# Connectors.net
KiCad netlist of a schematic drawn in Altium Designer
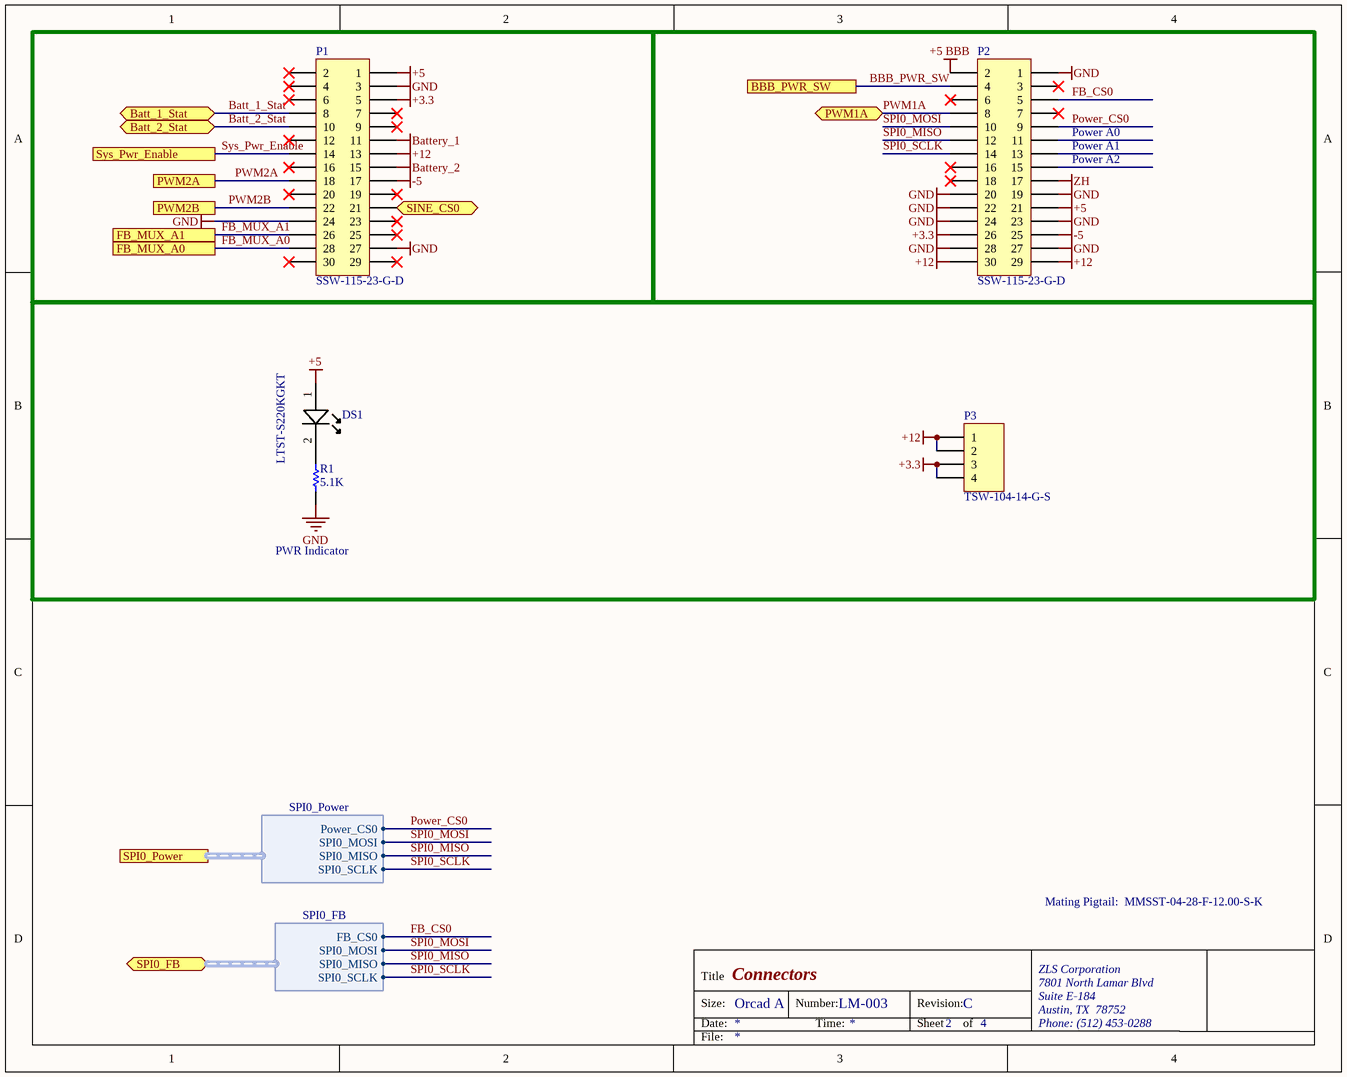
[diagram p0: Connectors.SchDoc]

(export (version "E")
  (design (tool "Eeschema 10.0.6"))
  (components
    (comp (ref "DS1")
      (value "Lite-On LTST-S220KGKT Green LED, 571 nm 2012 (0805) Side View, Rectangle Lens SMD package")
      (footprint "0805C_L")
      (fields
        (field (name "MANUFACTURER") "Vishay / Lite-On")
        (field (name "MANUFACTURER PART NUMBER") "LTST-S220KGKT")
      )
      (libsource (lib "*") (part "LED A/K"))
    )
    (comp (ref "P1")
      (value "SSW-115-23-G-D")
      (footprint "SSW-115-23-G-D")
      (description "Header, 15-Pin, Dual row")
      (fields (field (name "MANUFACTURER") "Samtec Inc."))
      (libsource (lib "Miscellaneous Connectors") (part "Header 15X2"))
    )
    (comp (ref "P2")
      (value "SSW-115-23-G-D")
      (footprint "SSW-115-23-G-D")
      (description "Header, 15-Pin, Dual row")
      (fields (field (name "MANUFACTURER") "Samtec Inc."))
      (libsource (lib "Miscellaneous Connectors") (part "Header 15X2"))
    )
    (comp (ref "P3")
      (value "TSW-104-14-G-S")
      (footprint "HDR1X4")
      (description "Header, 4-Pin")
      (fields (field (name "MANUFACTURER") "Samtec Inc."))
      (libsource (lib "Miscellaneous Connectors") (part "Header 4"))
    )
    (comp (ref "R1")
      (value "5.1K")
      (footprint "RESC0805(2012)_L")
      (description "RES SMD 5.1K OHM 5% 1/8W 0805")
      (fields
        (field (name "MANUFACTURER") "Vishay Dale")
        (field (name "MANUFACTURER PART NUMBER") "CRCW08055K10JNEA")
      )
      (libsource (lib "Altium Content Vault") (part "CMP-1013-00215-1"))
    )
  )
  (nets
    (net (code "3") (name "+3.3") (class "Default")
      (node (ref "P1") (pin "5") (pinfunction "5_5") (pintype "passive"))
      (node (ref "P2") (pin "26") (pinfunction "26_26") (pintype "passive"))
      (node (ref "P3") (pin "3") (pinfunction "3_3") (pintype "passive"))
      (node (ref "P3") (pin "4") (pinfunction "4_4") (pintype "passive"))
    )
    (net (code "4") (name "+5") (class "Default")
      (node (ref "DS1") (pin "1") (pinfunction "A_1") (pintype "passive"))
      (node (ref "P1") (pin "1") (pinfunction "1_1") (pintype "passive"))
      (node (ref "P2") (pin "21") (pinfunction "21_21") (pintype "passive"))
    )
    (net (code "5") (name "+5 BBB") (class "Default")
      (node (ref "P2") (pin "2") (pinfunction "2_2") (pintype "passive"))
    )
    (net (code "6") (name "+12") (class "Default")
      (node (ref "P1") (pin "13") (pinfunction "13_13") (pintype "passive"))
      (node (ref "P2") (pin "29") (pinfunction "29_29") (pintype "passive"))
      (node (ref "P2") (pin "30") (pinfunction "30_30") (pintype "passive"))
      (node (ref "P3") (pin "1") (pinfunction "1_1") (pintype "passive"))
      (node (ref "P3") (pin "2") (pinfunction "2_2") (pintype "passive"))
    )
    (net (code "7") (name "-5") (class "Default")
      (node (ref "P1") (pin "17") (pinfunction "17_17") (pintype "passive"))
      (node (ref "P2") (pin "25") (pinfunction "25_25") (pintype "passive"))
    )
    (net (code "8") (name "/BBB_PWR_SW") (class "Default")
      (node (ref "P2") (pin "4") (pinfunction "4_4") (pintype "passive"))
    )
    (net (code "9") (name "/Batt_1_Stat") (class "Default")
      (node (ref "P1") (pin "8") (pinfunction "8_8") (pintype "passive"))
    )
    (net (code "10") (name "/Batt_2_Stat") (class "Default")
      (node (ref "P1") (pin "10") (pinfunction "10_10") (pintype "passive"))
    )
    (net (code "11") (name "/FB_CS0") (class "Default")
      (node (ref "P2") (pin "5") (pinfunction "5_5") (pintype "passive"))
    )
    (net (code "12") (name "/FB_MUX_A0") (class "Default")
      (node (ref "P1") (pin "28") (pinfunction "28_28") (pintype "passive"))
    )
    (net (code "13") (name "/FB_MUX_A1") (class "Default")
      (node (ref "P1") (pin "26") (pinfunction "26_26") (pintype "passive"))
    )
    (net (code "14") (name "/PWM1A") (class "Default")
      (node (ref "P2") (pin "8") (pinfunction "8_8") (pintype "passive"))
    )
    (net (code "15") (name "/PWM2A") (class "Default")
      (node (ref "P1") (pin "18") (pinfunction "18_18") (pintype "passive"))
    )
    (net (code "16") (name "/PWM2B") (class "Default")
      (node (ref "P1") (pin "22") (pinfunction "22_22") (pintype "passive"))
    )
    (net (code "17") (name "/Power_CS0") (class "Default")
      (node (ref "P2") (pin "9") (pinfunction "9_9") (pintype "passive"))
    )
    (net (code "18") (name "/SINE_CS0") (class "Default")
      (node (ref "P1") (pin "21") (pinfunction "21_21") (pintype "passive"))
    )
    (net (code "19") (name "/SPI0_MISO") (class "Default")
      (node (ref "P2") (pin "12") (pinfunction "12_12") (pintype "passive"))
    )
    (net (code "20") (name "/SPI0_MOSI") (class "Default")
      (node (ref "P2") (pin "10") (pinfunction "10_10") (pintype "passive"))
    )
    (net (code "21") (name "/SPI0_SCLK") (class "Default")
      (node (ref "P2") (pin "14") (pinfunction "14_14") (pintype "passive"))
    )
    (net (code "22") (name "/Sys_Pwr_Enable") (class "Default")
      (node (ref "P1") (pin "14") (pinfunction "14_14") (pintype "passive"))
    )
    (net (code "25") (name "Battery_1") (class "Default")
      (node (ref "P1") (pin "11") (pinfunction "11_11") (pintype "passive"))
    )
    (net (code "26") (name "Battery_2") (class "Default")
      (node (ref "P1") (pin "15") (pinfunction "15_15") (pintype "passive"))
    )
    (net (code "27") (name "GND") (class "Default")
      (node (ref "P1") (pin "24") (pinfunction "24_24") (pintype "passive"))
      (node (ref "P1") (pin "27") (pinfunction "27_27") (pintype "passive"))
      (node (ref "P1") (pin "3") (pinfunction "3_3") (pintype "passive"))
      (node (ref "P2") (pin "1") (pinfunction "1_1") (pintype "passive"))
      (node (ref "P2") (pin "19") (pinfunction "19_19") (pintype "passive"))
      (node (ref "P2") (pin "20") (pinfunction "20_20") (pintype "passive"))
      (node (ref "P2") (pin "22") (pinfunction "22_22") (pintype "passive"))
      (node (ref "P2") (pin "23") (pinfunction "23_23") (pintype "passive"))
      (node (ref "P2") (pin "24") (pinfunction "24_24") (pintype "passive"))
      (node (ref "P2") (pin "27") (pinfunction "27_27") (pintype "passive"))
      (node (ref "P2") (pin "28") (pinfunction "28_28") (pintype "passive"))
      (node (ref "R1") (pin "2") (pinfunction "2_2") (pintype "passive"))
    )
    (net (code "28") (name "Net-(DS1-K)") (class "Default")
      (node (ref "DS1") (pin "2") (pinfunction "K_2") (pintype "passive"))
      (node (ref "R1") (pin "1") (pinfunction "1_1") (pintype "passive"))
    )
    (net (code "29") (name "ZH") (class "Default")
      (node (ref "P2") (pin "17") (pinfunction "17_17") (pintype "passive"))
    )
    (net (code "30") (name "unconnected-(P1-Pad2)") (class "Default")
      (node (ref "P1") (pin "2") (pinfunction "2_2") (pintype "passive+no_connect"))
    )
    (net (code "31") (name "unconnected-(P1-Pad4)") (class "Default")
      (node (ref "P1") (pin "4") (pinfunction "4_4") (pintype "passive+no_connect"))
    )
    (net (code "32") (name "unconnected-(P1-Pad6)") (class "Default")
      (node (ref "P1") (pin "6") (pinfunction "6_6") (pintype "passive+no_connect"))
    )
    (net (code "33") (name "unconnected-(P1-Pad7)") (class "Default")
      (node (ref "P1") (pin "7") (pinfunction "7_7") (pintype "passive+no_connect"))
    )
    (net (code "34") (name "unconnected-(P1-Pad9)") (class "Default")
      (node (ref "P1") (pin "9") (pinfunction "9_9") (pintype "passive+no_connect"))
    )
    (net (code "35") (name "unconnected-(P1-Pad12)") (class "Default")
      (node (ref "P1") (pin "12") (pinfunction "12_12") (pintype "passive+no_connect"))
    )
    (net (code "36") (name "unconnected-(P1-Pad16)") (class "Default")
      (node (ref "P1") (pin "16") (pinfunction "16_16") (pintype "passive+no_connect"))
    )
    (net (code "37") (name "unconnected-(P1-Pad19)") (class "Default")
      (node (ref "P1") (pin "19") (pinfunction "19_19") (pintype "passive+no_connect"))
    )
    (net (code "38") (name "unconnected-(P1-Pad20)") (class "Default")
      (node (ref "P1") (pin "20") (pinfunction "20_20") (pintype "passive+no_connect"))
    )
    (net (code "39") (name "unconnected-(P1-Pad23)") (class "Default")
      (node (ref "P1") (pin "23") (pinfunction "23_23") (pintype "passive+no_connect"))
    )
    (net (code "40") (name "unconnected-(P1-Pad25)") (class "Default")
      (node (ref "P1") (pin "25") (pinfunction "25_25") (pintype "passive+no_connect"))
    )
    (net (code "41") (name "unconnected-(P1-Pad29)") (class "Default")
      (node (ref "P1") (pin "29") (pinfunction "29_29") (pintype "passive+no_connect"))
    )
    (net (code "42") (name "unconnected-(P1-Pad30)") (class "Default")
      (node (ref "P1") (pin "30") (pinfunction "30_30") (pintype "passive+no_connect"))
    )
    (net (code "43") (name "unconnected-(P2-Pad3)") (class "Default")
      (node (ref "P2") (pin "3") (pinfunction "3_3") (pintype "passive+no_connect"))
    )
    (net (code "44") (name "unconnected-(P2-Pad6)") (class "Default")
      (node (ref "P2") (pin "6") (pinfunction "6_6") (pintype "passive+no_connect"))
    )
    (net (code "45") (name "unconnected-(P2-Pad7)") (class "Default")
      (node (ref "P2") (pin "7") (pinfunction "7_7") (pintype "passive+no_connect"))
    )
    (net (code "46") (name "unconnected-(P2-Pad11)") (class "Default")
      (node (ref "P2") (pin "11") (pinfunction "11_11") (pintype "passive"))
    )
    (net (code "47") (name "unconnected-(P2-Pad13)") (class "Default")
      (node (ref "P2") (pin "13") (pinfunction "13_13") (pintype "passive"))
    )
    (net (code "48") (name "unconnected-(P2-Pad15)") (class "Default")
      (node (ref "P2") (pin "15") (pinfunction "15_15") (pintype "passive"))
    )
    (net (code "49") (name "unconnected-(P2-Pad16)") (class "Default")
      (node (ref "P2") (pin "16") (pinfunction "16_16") (pintype "passive+no_connect"))
    )
    (net (code "50") (name "unconnected-(P2-Pad18)") (class "Default")
      (node (ref "P2") (pin "18") (pinfunction "18_18") (pintype "passive+no_connect"))
    )
  )
)
